# Schematic.net
KiCad netlist of a schematic drawn in EAGLE
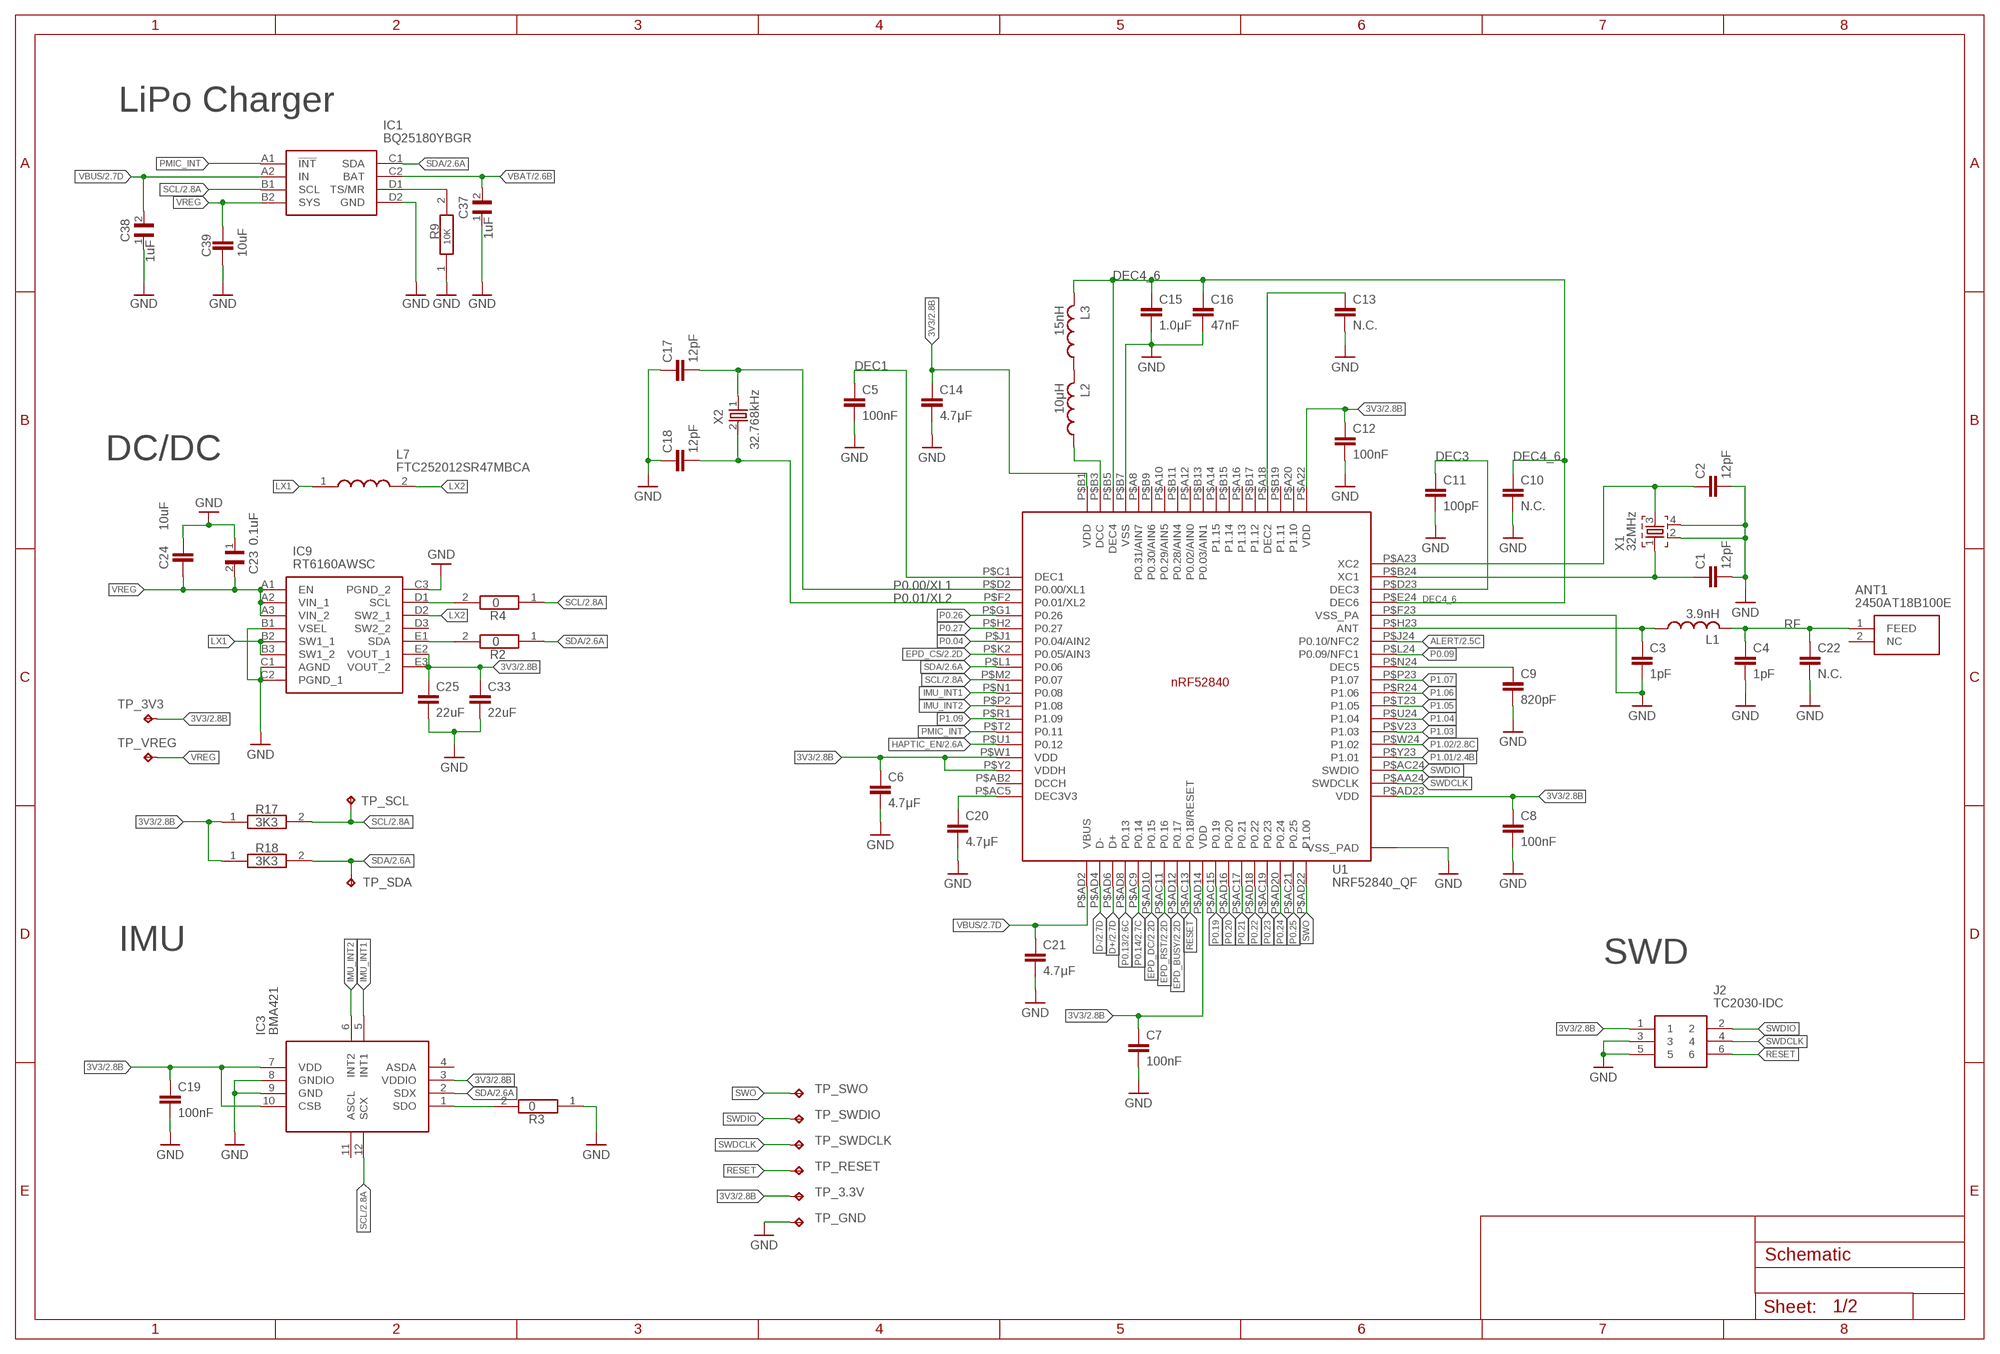
[diagram p0: schematic, sheet 1]
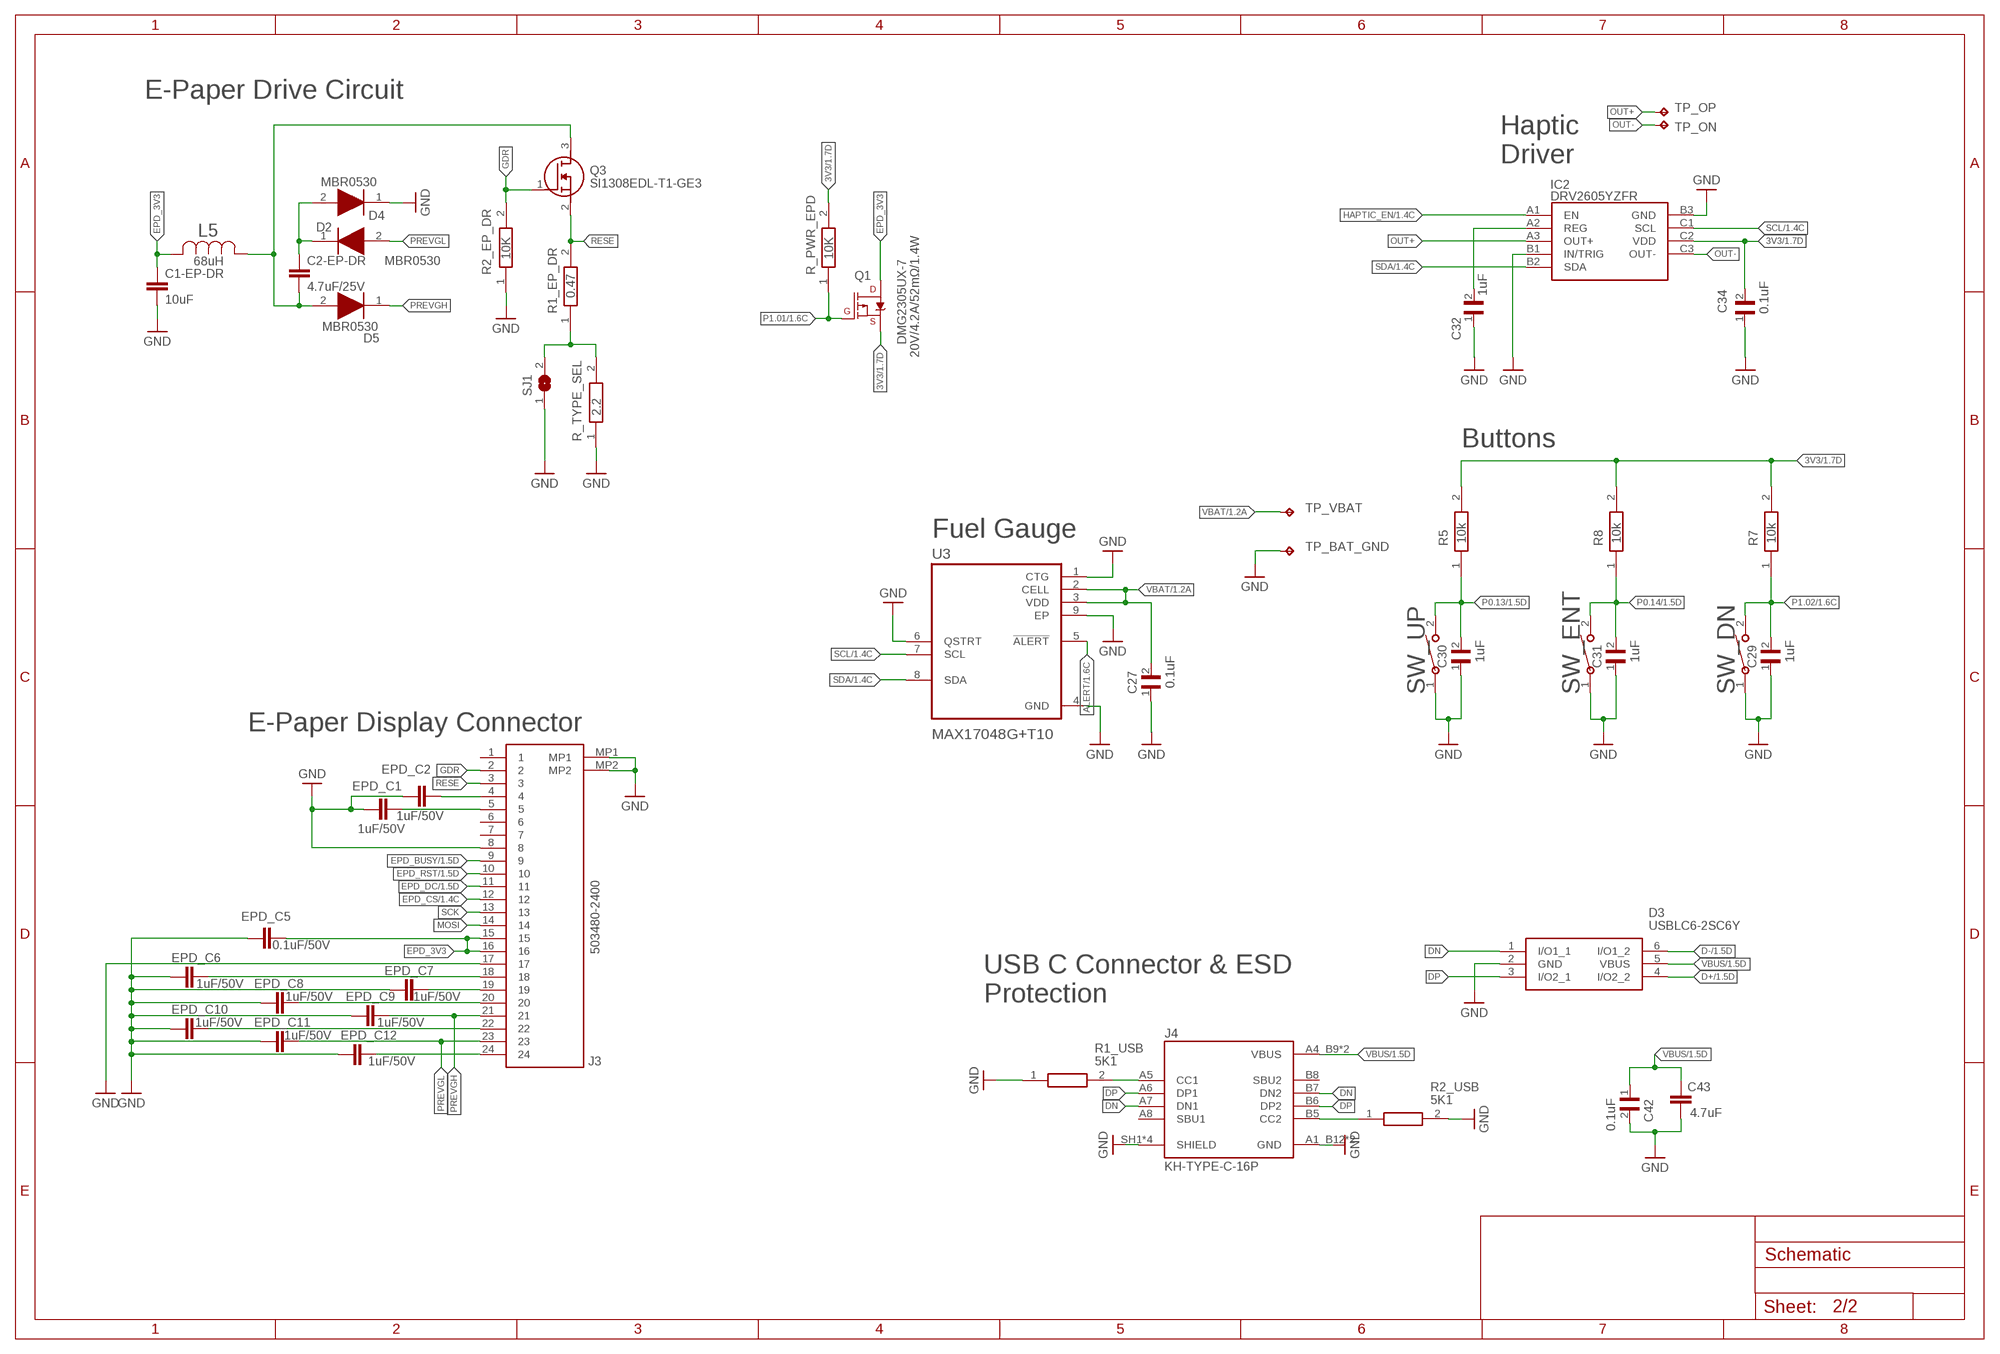
[diagram p1: schematic, sheet 2]

(export (version "E")
  (design (tool "Eeschema 10.0.6"))
  (components
    (comp (ref "C1-EP-DR")
      (value "10uF")
      (footprint "eagle-import:PERFECT_0402_0402")
      (libsource (lib "eagle-import") (part "PERFECT_0402_CAP_0402"))
    )
    (comp (ref "C2-EP-DR")
      (value "4.7uF/25V")
      (footprint "eagle-import:PERFECT_0402_0402")
      (libsource (lib "eagle-import") (part "PERFECT_0402_CAP_0402"))
    )
    (comp (ref "C27")
      (value "0.1uF")
      (footprint "eagle-import:GRM011R60J152KE01L_1_0201")
      (libsource (lib "eagle-import") (part "GRM011R60J152KE01L_1_GRM011R60J152KE01L"))
    )
    (comp (ref "C29")
      (value "1uF")
      (footprint "eagle-import:GRM011R60J152KE01L_1_0201")
      (libsource (lib "eagle-import") (part "GRM011R60J152KE01L_1_GRM011R60J152KE01L"))
    )
    (comp (ref "C30")
      (value "1uF")
      (footprint "eagle-import:GRM011R60J152KE01L_1_0201")
      (libsource (lib "eagle-import") (part "GRM011R60J152KE01L_1_GRM011R60J152KE01L"))
    )
    (comp (ref "C31")
      (value "1uF")
      (footprint "eagle-import:GRM011R60J152KE01L_1_0201")
      (libsource (lib "eagle-import") (part "GRM011R60J152KE01L_1_GRM011R60J152KE01L"))
    )
    (comp (ref "C32")
      (value "1uF")
      (footprint "eagle-import:GRM011R60J152KE01L_1_0201")
      (libsource (lib "eagle-import") (part "GRM011R60J152KE01L_1_GRM011R60J152KE01L"))
    )
    (comp (ref "C34")
      (value "0.1uF")
      (footprint "eagle-import:GRM011R60J152KE01L_1_0201")
      (libsource (lib "eagle-import") (part "GRM011R60J152KE01L_1_GRM011R60J152KE01L"))
    )
    (comp (ref "C42")
      (value "0.1uF")
      (footprint "eagle-import:GRM011R60J152KE01L_1_0201")
      (libsource (lib "eagle-import") (part "GRM011R60J152KE01L_1_GRM011R60J152KE01L"))
    )
    (comp (ref "C43")
      (value "4.7uF")
      (footprint "eagle-import:PERFECT_0402_0402")
      (libsource (lib "eagle-import") (part "PERFECT_0402_CAP_0402"))
    )
    (comp (ref "D2")
      (value "MBR0530")
      (footprint "eagle-import:ESP32_C6_LIBRARY_5_SOD3716X135N")
      (fields (field (name "MF") "ON Semiconductor"))
      (libsource (lib "eagle-import") (part "ESP32_C6_LIBRARY_5_MBR0530"))
    )
    (comp (ref "D3")
      (value "USBLC6-2SC6Y")
      (footprint "eagle-import:ESP32_C6_LIBRARY_3_SOT95P280X145-6N")
      (fields (field (name "MF") "STMicroelectronics"))
      (libsource (lib "eagle-import") (part "ESP32_C6_LIBRARY_3_USBLC6-2SC6Y"))
    )
    (comp (ref "D4")
      (value "MBR0530")
      (footprint "eagle-import:ESP32_C6_LIBRARY_5_SOD3716X135N")
      (fields (field (name "MF") "ON Semiconductor"))
      (libsource (lib "eagle-import") (part "ESP32_C6_LIBRARY_5_MBR0530"))
    )
    (comp (ref "D5")
      (value "MBR0530")
      (footprint "eagle-import:ESP32_C6_LIBRARY_5_SOD3716X135N")
      (fields (field (name "MF") "ON Semiconductor"))
      (libsource (lib "eagle-import") (part "ESP32_C6_LIBRARY_5_MBR0530"))
    )
    (comp (ref "EPD_C1")
      (value "1uF/50V")
      (footprint "eagle-import:PERFECT_0402_0402")
      (libsource (lib "eagle-import") (part "PERFECT_0402_CAP_0402"))
    )
    (comp (ref "EPD_C2")
      (value "1uF/50V")
      (footprint "eagle-import:PERFECT_0402_0402")
      (libsource (lib "eagle-import") (part "PERFECT_0402_CAP_0402"))
    )
    (comp (ref "EPD_C5")
      (value "0.1uF/50V")
      (footprint "eagle-import:PERFECT_0402_0402")
      (libsource (lib "eagle-import") (part "PERFECT_0402_CAP_0402"))
    )
    (comp (ref "EPD_C6")
      (value "1uF/50V")
      (footprint "eagle-import:PERFECT_0402_0402")
      (libsource (lib "eagle-import") (part "PERFECT_0402_CAP_0402"))
    )
    (comp (ref "EPD_C7")
      (value "1uF/50V")
      (footprint "eagle-import:PERFECT_0402_0402")
      (libsource (lib "eagle-import") (part "PERFECT_0402_CAP_0402"))
    )
    (comp (ref "EPD_C8")
      (value "1uF/50V")
      (footprint "eagle-import:PERFECT_0402_0402")
      (libsource (lib "eagle-import") (part "PERFECT_0402_CAP_0402"))
    )
    (comp (ref "EPD_C9")
      (value "1uF/50V")
      (footprint "eagle-import:PERFECT_0402_0402")
      (libsource (lib "eagle-import") (part "PERFECT_0402_CAP_0402"))
    )
    (comp (ref "EPD_C10")
      (value "1uF/50V")
      (footprint "eagle-import:PERFECT_0402_0402")
      (libsource (lib "eagle-import") (part "PERFECT_0402_CAP_0402"))
    )
    (comp (ref "EPD_C11")
      (value "1uF/50V")
      (footprint "eagle-import:PERFECT_0402_0402")
      (libsource (lib "eagle-import") (part "PERFECT_0402_CAP_0402"))
    )
    (comp (ref "EPD_C12")
      (value "1uF/50V")
      (footprint "eagle-import:PERFECT_0402_0402")
      (libsource (lib "eagle-import") (part "PERFECT_0402_CAP_0402"))
    )
    (comp (ref "IC2")
      (value "DRV2605YZFR")
      (footprint "eagle-import:DRV2605YZFR_BGA9C50P3X3_144X144X62")
      (libsource (lib "eagle-import") (part "DRV2605YZFR_DRV2605YZFR"))
    )
    (comp (ref "J3")
      (value "503480-2400")
      (footprint "eagle-import:503480-2400_5034802400")
      (fields (field (name "MOUSER_PART_NUMBER") "538-503480-2400"))
      (libsource (lib "eagle-import") (part "503480-2400_503480-2400"))
    )
    (comp (ref "J4")
      (value "KH-TYPE-C-16P")
      (footprint "eagle-import:KH-TYPE-C-16P_KINGHELM_KH-TYPE-C-16P")
      (fields (field (name "MF") "kinghelm"))
      (libsource (lib "eagle-import") (part "KH-TYPE-C-16P_KH-TYPE-C-16P"))
    )
    (comp (ref "L5")
      (value "68uH")
      (footprint "eagle-import:ESP32_C6_LIBRARY_2_IND_4828-WE-TPC_WRE")
      (fields
        (field (name "MANUFACTURER_PART_NUMBER") "744043680")
        (field (name "COPYRIGHT") "Copyright (C) 2024 Ultra Librarian. All rights reserved.")
      )
      (libsource (lib "eagle-import") (part "ESP32_C6_LIBRARY_2_744043680IND_4828-WE-TPC_WRE"))
    )
    (comp (ref "Q1")
      (value "20V/4.2A/52mΩ/1.4W")
      (footprint "eagle-import:ESP32_C6_LIBRARY_4_ESP32_C6_LIBRARY_4_ESP32_C6_LIBRARY_4_ESP32_C6_LIBRARY_4_ESP32_WROVER_SPARKFUN-DISCRETESEMI_SOT23-3")
      (libsource (lib "eagle-import") (part "ESP32_C6_LIBRARY_4_ESP32_WROVER_SPARKFUN-DISCRETESEMI_MOSFET_PCH-DMG2305UX-7"))
    )
    (comp (ref "Q3")
      (value "SI1308EDL-T1-GE3")
      (footprint "eagle-import:ESP32_C6_LIBRARY_6_SOT65P210X110-3N")
      (fields (field (name "MF") "Vishay Siliconix"))
      (libsource (lib "eagle-import") (part "ESP32_C6_LIBRARY_6_SI1308EDL-T1-GE3"))
    )
    (comp (ref "R1_EP_DR")
      (value "0.47")
      (footprint "eagle-import:CPF0201D7K68C1_0201")
      (libsource (lib "eagle-import") (part "CPF0201D7K68C1_CPF0201D7K68C1"))
    )
    (comp (ref "R1_USB")
      (value "5K1")
      (footprint "eagle-import:CPF0201D7K68C1_0201")
      (libsource (lib "eagle-import") (part "CPF0201D7K68C1_CPF0201D7K68C1"))
    )
    (comp (ref "R2_EP_DR")
      (value "10K")
      (footprint "eagle-import:CPF0201D7K68C1_0201")
      (libsource (lib "eagle-import") (part "CPF0201D7K68C1_CPF0201D7K68C1"))
    )
    (comp (ref "R2_USB")
      (value "5K1")
      (footprint "eagle-import:CPF0201D7K68C1_0201")
      (libsource (lib "eagle-import") (part "CPF0201D7K68C1_CPF0201D7K68C1"))
    )
    (comp (ref "R5")
      (value "10k")
      (footprint "eagle-import:CPF0201D7K68C1_0201")
      (libsource (lib "eagle-import") (part "CPF0201D7K68C1_CPF0201D7K68C1"))
    )
    (comp (ref "R7")
      (value "10k")
      (footprint "eagle-import:CPF0201D7K68C1_0201")
      (libsource (lib "eagle-import") (part "CPF0201D7K68C1_CPF0201D7K68C1"))
    )
    (comp (ref "R8")
      (value "10k")
      (footprint "eagle-import:CPF0201D7K68C1_0201")
      (libsource (lib "eagle-import") (part "CPF0201D7K68C1_CPF0201D7K68C1"))
    )
    (comp (ref "R_PWR_EPD")
      (value "10K")
      (footprint "eagle-import:CPF0201D7K68C1_0201")
      (libsource (lib "eagle-import") (part "CPF0201D7K68C1_CPF0201D7K68C1"))
    )
    (comp (ref "R_TYPE_SEL")
      (value "2.2")
      (footprint "eagle-import:CPF0201D7K68C1_0201")
      (libsource (lib "eagle-import") (part "CPF0201D7K68C1_CPF0201D7K68C1"))
    )
    (comp (ref "SJ1")
      (value "ESP32_C6_LIBRARY_7_JUMPER_SJ")
      (footprint "eagle-import:ESP32_C6_LIBRARY_7_JUMPER_SJ")
      (libsource (lib "eagle-import") (part "ESP32_C6_LIBRARY_7_JUMPER_SJ"))
    )
    (comp (ref "SW_DN")
      (value "2025-10-22_07-23-44_LIBRARY_EVP-AKE31ASW_EVP-AKE31A_PAN")
      (footprint "eagle-import:2025-10-22_07-23-44_LIBRARY_SW_EVP-AKE31A_PAN")
      (fields
        (field (name "MANUFACTURER_PART_NUMBER") "EVP-AKE31A")
        (field (name "COPYRIGHT") "Copyright (C) 2025 Ultra Librarian. All rights reserved.")
      )
      (libsource (lib "eagle-import") (part "2025-10-22_07-23-44_LIBRARY_EVP-AKE31ASW_EVP-AKE31A_PAN"))
    )
    (comp (ref "SW_ENT")
      (value "2025-10-22_07-23-44_LIBRARY_EVP-AKE31ASW_EVP-AKE31A_PAN")
      (footprint "eagle-import:2025-10-22_07-23-44_LIBRARY_SW_EVP-AKE31A_PAN")
      (fields
        (field (name "MANUFACTURER_PART_NUMBER") "EVP-AKE31A")
        (field (name "COPYRIGHT") "Copyright (C) 2025 Ultra Librarian. All rights reserved.")
      )
      (libsource (lib "eagle-import") (part "2025-10-22_07-23-44_LIBRARY_EVP-AKE31ASW_EVP-AKE31A_PAN"))
    )
    (comp (ref "SW_UP")
      (value "2025-10-22_07-23-44_LIBRARY_EVP-AKE31ASW_EVP-AKE31A_PAN")
      (footprint "eagle-import:2025-10-22_07-23-44_LIBRARY_SW_EVP-AKE31A_PAN")
      (fields
        (field (name "MANUFACTURER_PART_NUMBER") "EVP-AKE31A")
        (field (name "COPYRIGHT") "Copyright (C) 2025 Ultra Librarian. All rights reserved.")
      )
      (libsource (lib "eagle-import") (part "2025-10-22_07-23-44_LIBRARY_EVP-AKE31ASW_EVP-AKE31A_PAN"))
    )
    (comp (ref "TP_BAT_GND")
      (value "HECTOR_WATCH_1_TPTP20R")
      (footprint "eagle-import:HECTOR_WATCH_1_TP20R")
      (libsource (lib "eagle-import") (part "HECTOR_WATCH_1_TPTP20R"))
    )
    (comp (ref "TP_ON")
      (value "HECTOR_WATCH_1_TPTP20R")
      (footprint "eagle-import:HECTOR_WATCH_1_TP20R")
      (libsource (lib "eagle-import") (part "HECTOR_WATCH_1_TPTP20R"))
    )
    (comp (ref "TP_OP")
      (value "HECTOR_WATCH_1_TPTP20R")
      (footprint "eagle-import:HECTOR_WATCH_1_TP20R")
      (libsource (lib "eagle-import") (part "HECTOR_WATCH_1_TPTP20R"))
    )
    (comp (ref "TP_VBAT")
      (value "HECTOR_WATCH_1_TPTP20R")
      (footprint "eagle-import:HECTOR_WATCH_1_TP20R")
      (libsource (lib "eagle-import") (part "HECTOR_WATCH_1_TPTP20R"))
    )
    (comp (ref "U3")
      (value "MAX17048G+T10")
      (footprint "eagle-import:ESP32_C6_LIBRARY_SON50P200X200X80-9N")
      (fields (field (name "MF") "Analog Devices"))
      (libsource (lib "eagle-import") (part "ESP32_C6_LIBRARY_MAX17048G+T10"))
    )
    (comp (ref "ANT1")
      (value "2450AT18B100E")
      (footprint "eagle-import:2450AT18B100E_ANTC3216X140N")
      (fields (field (name "MOUSER_PART_NUMBER") "609-2450AT18B100E"))
      (libsource (lib "eagle-import") (part "2450AT18B100E_2450AT18B100E"))
    )
    (comp (ref "C1")
      (value "12pF")
      (footprint "eagle-import:PERFECT_0402_0402")
      (libsource (lib "eagle-import") (part "PERFECT_0402_CAP_0402"))
    )
    (comp (ref "C2")
      (value "12pF")
      (footprint "eagle-import:PERFECT_0402_0402")
      (libsource (lib "eagle-import") (part "PERFECT_0402_CAP_0402"))
    )
    (comp (ref "C3")
      (value "1pF")
      (footprint "eagle-import:PERFECT_0402_0402")
      (libsource (lib "eagle-import") (part "PERFECT_0402_CAP_0402"))
    )
    (comp (ref "C4")
      (value "1pF")
      (footprint "eagle-import:PERFECT_0402_0402")
      (libsource (lib "eagle-import") (part "PERFECT_0402_CAP_0402"))
    )
    (comp (ref "C5")
      (value "100nF")
      (footprint "eagle-import:PERFECT_0402_0402")
      (libsource (lib "eagle-import") (part "PERFECT_0402_CAP_0402"))
    )
    (comp (ref "C6")
      (value "4.7μF")
      (footprint "eagle-import:PERFECT_0402_0402")
      (libsource (lib "eagle-import") (part "PERFECT_0402_CAP_0402"))
    )
    (comp (ref "C7")
      (value "100nF")
      (footprint "eagle-import:PERFECT_0402_0402")
      (libsource (lib "eagle-import") (part "PERFECT_0402_CAP_0402"))
    )
    (comp (ref "C8")
      (value "100nF")
      (footprint "eagle-import:PERFECT_0402_0402")
      (libsource (lib "eagle-import") (part "PERFECT_0402_CAP_0402"))
    )
    (comp (ref "C9")
      (value "820pF")
      (footprint "eagle-import:PERFECT_0402_0402")
      (libsource (lib "eagle-import") (part "PERFECT_0402_CAP_0402"))
    )
    (comp (ref "C10")
      (value "N.C.")
      (footprint "eagle-import:PERFECT_0402_0402")
      (libsource (lib "eagle-import") (part "PERFECT_0402_CAP_0402"))
    )
    (comp (ref "C11")
      (value "100pF")
      (footprint "eagle-import:PERFECT_0402_0402")
      (libsource (lib "eagle-import") (part "PERFECT_0402_CAP_0402"))
    )
    (comp (ref "C12")
      (value "100nF")
      (footprint "eagle-import:PERFECT_0402_0402")
      (libsource (lib "eagle-import") (part "PERFECT_0402_CAP_0402"))
    )
    (comp (ref "C13")
      (value "N.C.")
      (footprint "eagle-import:PERFECT_0402_0402")
      (libsource (lib "eagle-import") (part "PERFECT_0402_CAP_0402"))
    )
    (comp (ref "C14")
      (value "4.7μF")
      (footprint "eagle-import:PERFECT_0402_0402")
      (libsource (lib "eagle-import") (part "PERFECT_0402_CAP_0402"))
    )
    (comp (ref "C15")
      (value "1.0μF")
      (footprint "eagle-import:PERFECT_0402_0402")
      (libsource (lib "eagle-import") (part "PERFECT_0402_CAP_0402"))
    )
    (comp (ref "C16")
      (value "47nF")
      (footprint "eagle-import:PERFECT_0402_0402")
      (libsource (lib "eagle-import") (part "PERFECT_0402_CAP_0402"))
    )
    (comp (ref "C17")
      (value "12pF")
      (footprint "eagle-import:PERFECT_0402_0402")
      (libsource (lib "eagle-import") (part "PERFECT_0402_CAP_0402"))
    )
    (comp (ref "C18")
      (value "12pF")
      (footprint "eagle-import:PERFECT_0402_0402")
      (libsource (lib "eagle-import") (part "PERFECT_0402_CAP_0402"))
    )
    (comp (ref "C19")
      (value "100nF")
      (footprint "eagle-import:PERFECT_0402_0402")
      (libsource (lib "eagle-import") (part "PERFECT_0402_CAP_0402"))
    )
    (comp (ref "C20")
      (value "4.7μF")
      (footprint "eagle-import:PERFECT_0402_0402")
      (libsource (lib "eagle-import") (part "PERFECT_0402_CAP_0402"))
    )
    (comp (ref "C21")
      (value "4.7μF")
      (footprint "eagle-import:PERFECT_0402_0402")
      (libsource (lib "eagle-import") (part "PERFECT_0402_CAP_0402"))
    )
    (comp (ref "C22")
      (value "N.C.")
      (footprint "eagle-import:PERFECT_0402_0402")
      (libsource (lib "eagle-import") (part "PERFECT_0402_CAP_0402"))
    )
    (comp (ref "C23")
      (value "0.1uF")
      (footprint "eagle-import:GRM011R60J152KE01L_1_0201")
      (libsource (lib "eagle-import") (part "GRM011R60J152KE01L_1_GRM011R60J152KE01L"))
    )
    (comp (ref "C24")
      (value "10uF")
      (footprint "eagle-import:PERFECT_0402_0402")
      (libsource (lib "eagle-import") (part "PERFECT_0402_CAP_0402"))
    )
    (comp (ref "C25")
      (value "22uF")
      (footprint "eagle-import:PERFECT_0402_0402")
      (libsource (lib "eagle-import") (part "PERFECT_0402_CAP_0402"))
    )
    (comp (ref "C33")
      (value "22uF")
      (footprint "eagle-import:PERFECT_0402_0402")
      (libsource (lib "eagle-import") (part "PERFECT_0402_CAP_0402"))
    )
    (comp (ref "C37")
      (value "1uF")
      (footprint "eagle-import:GRM011R60J152KE01L_1_0201")
      (libsource (lib "eagle-import") (part "GRM011R60J152KE01L_1_GRM011R60J152KE01L"))
    )
    (comp (ref "C38")
      (value "1uF")
      (footprint "eagle-import:GRM011R60J152KE01L_1_0201")
      (libsource (lib "eagle-import") (part "GRM011R60J152KE01L_1_GRM011R60J152KE01L"))
    )
    (comp (ref "C39")
      (value "10uF")
      (footprint "eagle-import:NORDIC_NRF_3_RESC0402_N")
      (libsource (lib "eagle-import") (part "NORDIC_NRF_3_CAPACITOR_0402_N"))
    )
    (comp (ref "IC1")
      (value "BQ25180YBGR")
      (footprint "eagle-import:BQ25180YBGR_BGA8C40P2X4_100X155X50")
      (fields (field (name "MOUSER_PART_NUMBER") "595-BQ25180YBGR"))
      (libsource (lib "eagle-import") (part "BQ25180YBGR_BQ25180YBGR"))
    )
    (comp (ref "IC3")
      (value "BMA421")
      (footprint "eagle-import:BMA423_BMA423")
      (fields (field (name "ARROW_PART_NUMBER") "BMA423") (field (name "MOUSER_PART_NUMBER") "262-BMA423"))
      (libsource (lib "eagle-import") (part "BMA423_BMA423"))
    )
    (comp (ref "IC9")
      (value "RT6160AWSC")
      (footprint "eagle-import:RT6160AWSC_BGA15C40P3X5_140X230X60")
      (fields (field (name "MOUSER_PART_NUMBER") "835-RT6160AWSC"))
      (libsource (lib "eagle-import") (part "RT6160AWSC_RT6160AWSC"))
    )
    (comp (ref "J2")
      (value "TC2030-IDC")
      (footprint "eagle-import:TC2030-IDC_TC2030IDC")
      (libsource (lib "eagle-import") (part "TC2030-IDC_TC2030-IDC"))
    )
    (comp (ref "L1")
      (value "3.9nH")
      (footprint "eagle-import:NORDIC_NRF_2_RESC0402_L")
      (libsource (lib "eagle-import") (part "NORDIC_NRF_2_INDUCTOR_0402_L"))
    )
    (comp (ref "L2")
      (value "10μH")
      (footprint "eagle-import:NORDIC_NRF_2_RESC0402_L")
      (libsource (lib "eagle-import") (part "NORDIC_NRF_2_INDUCTOR_0402_L"))
    )
    (comp (ref "L3")
      (value "15nH")
      (footprint "eagle-import:NORDIC_NRF_2_RESC0402_L")
      (libsource (lib "eagle-import") (part "NORDIC_NRF_2_INDUCTOR_0402_L"))
    )
    (comp (ref "L7")
      (value "FTC252012SR47MBCA")
      (footprint "eagle-import:MLP2016SR47MT0S1_INDC2016X100N")
      (libsource (lib "eagle-import") (part "MLP2016SR47MT0S1_FTC252012SR47MBCA"))
    )
    (comp (ref "R2")
      (value "0")
      (footprint "eagle-import:CPF0201D7K68C1_0201")
      (libsource (lib "eagle-import") (part "CPF0201D7K68C1_CPF0201D7K68C1"))
    )
    (comp (ref "R3")
      (value "0")
      (footprint "eagle-import:CPF0201D7K68C1_0201")
      (libsource (lib "eagle-import") (part "CPF0201D7K68C1_CPF0201D7K68C1"))
    )
    (comp (ref "R4")
      (value "0")
      (footprint "eagle-import:CPF0201D7K68C1_0201")
      (libsource (lib "eagle-import") (part "CPF0201D7K68C1_CPF0201D7K68C1"))
    )
    (comp (ref "R9")
      (value "10K")
      (footprint "eagle-import:CPF0201D7K68C1_0201")
      (libsource (lib "eagle-import") (part "CPF0201D7K68C1_CPF0201D7K68C1"))
    )
    (comp (ref "R17")
      (value "3K3")
      (footprint "eagle-import:CPF0201D7K68C1_0201")
      (libsource (lib "eagle-import") (part "CPF0201D7K68C1_CPF0201D7K68C1"))
    )
    (comp (ref "R18")
      (value "3K3")
      (footprint "eagle-import:CPF0201D7K68C1_0201")
      (libsource (lib "eagle-import") (part "CPF0201D7K68C1_CPF0201D7K68C1"))
    )
    (comp (ref "TP_3.3V")
      (value "HECTOR_WATCH_1_TPTP20R")
      (footprint "eagle-import:HECTOR_WATCH_1_TP20R")
      (libsource (lib "eagle-import") (part "HECTOR_WATCH_1_TPTP20R"))
    )
    (comp (ref "TP_3V3")
      (value "HECTOR_WATCH_1_TPTP20R")
      (footprint "eagle-import:HECTOR_WATCH_1_TP20R")
      (libsource (lib "eagle-import") (part "HECTOR_WATCH_1_TPTP20R"))
    )
    (comp (ref "TP_GND")
      (value "HECTOR_WATCH_1_TPTP20R")
      (footprint "eagle-import:HECTOR_WATCH_1_TP20R")
      (libsource (lib "eagle-import") (part "HECTOR_WATCH_1_TPTP20R"))
    )
    (comp (ref "TP_RESET")
      (value "HECTOR_WATCH_1_TPTP20R")
      (footprint "eagle-import:HECTOR_WATCH_1_TP20R")
      (libsource (lib "eagle-import") (part "HECTOR_WATCH_1_TPTP20R"))
    )
    (comp (ref "TP_SCL")
      (value "HECTOR_WATCH_1_TPTP20R")
      (footprint "eagle-import:HECTOR_WATCH_1_TP20R")
      (libsource (lib "eagle-import") (part "HECTOR_WATCH_1_TPTP20R"))
    )
    (comp (ref "TP_SDA")
      (value "HECTOR_WATCH_1_TPTP20R")
      (footprint "eagle-import:HECTOR_WATCH_1_TP20R")
      (libsource (lib "eagle-import") (part "HECTOR_WATCH_1_TPTP20R"))
    )
    (comp (ref "TP_SWDCLK")
      (value "HECTOR_WATCH_1_TPTP20R")
      (footprint "eagle-import:HECTOR_WATCH_1_TP20R")
      (libsource (lib "eagle-import") (part "HECTOR_WATCH_1_TPTP20R"))
    )
    (comp (ref "TP_SWDIO")
      (value "HECTOR_WATCH_1_TPTP20R")
      (footprint "eagle-import:HECTOR_WATCH_1_TP20R")
      (libsource (lib "eagle-import") (part "HECTOR_WATCH_1_TPTP20R"))
    )
    (comp (ref "TP_SWO")
      (value "HECTOR_WATCH_1_TPTP20R")
      (footprint "eagle-import:HECTOR_WATCH_1_TP20R")
      (libsource (lib "eagle-import") (part "HECTOR_WATCH_1_TPTP20R"))
    )
    (comp (ref "TP_VREG")
      (value "HECTOR_WATCH_1_TPTP20R")
      (footprint "eagle-import:HECTOR_WATCH_1_TP20R")
      (libsource (lib "eagle-import") (part "HECTOR_WATCH_1_TPTP20R"))
    )
    (comp (ref "U1")
      (value "NRF52840_QF")
      (footprint "eagle-import:NORDIC_NRF_4_AQFN50P700X700X85_HS-74N")
      (libsource (lib "eagle-import") (part "NORDIC_NRF_4_NRF52840_QF"))
    )
    (comp (ref "X1")
      (value "32MHz")
      (footprint "eagle-import:NORDIC_NRF_BT-XTAL_2016_N")
      (libsource (lib "eagle-import") (part "NORDIC_NRF_XTAL_32MHZ"))
    )
    (comp (ref "X2")
      (value "32.768kHz")
      (footprint "eagle-import:NORDIC_NRF_1_XTAL_3215_N")
      (libsource (lib "eagle-import") (part "NORDIC_NRF_1_XTAL_32KHZ"))
    )
  )
  (nets
    (net (code "1") (name "3V3") (class "Default")
      (node (ref "C12") (pin "1") (pinfunction "1_1") (pintype "passive"))
      (node (ref "C14") (pin "1") (pinfunction "1_1") (pintype "passive"))
      (node (ref "C19") (pin "1") (pinfunction "1_1") (pintype "passive"))
      (node (ref "C25") (pin "1") (pinfunction "1_1") (pintype "passive"))
      (node (ref "C33") (pin "1") (pinfunction "1_1") (pintype "passive"))
      (node (ref "C34") (pin "2") (pinfunction "2_2") (pintype "passive"))
      (node (ref "C6") (pin "1") (pinfunction "1_1") (pintype "passive"))
      (node (ref "C7") (pin "1") (pinfunction "1_1") (pintype "passive"))
      (node (ref "C8") (pin "1") (pinfunction "1_1") (pintype "passive"))
      (node (ref "IC2") (pin "C2") (pinfunction "VDD_C2") (pintype "bidirectional"))
      (node (ref "IC3") (pin "10") (pinfunction "CSB_10") (pintype "bidirectional"))
      (node (ref "IC3") (pin "3") (pinfunction "VDDIO_3") (pintype "bidirectional"))
      (node (ref "IC3") (pin "7") (pinfunction "VDD_7") (pintype "bidirectional"))
      (node (ref "IC9") (pin "E2") (pinfunction "VOUT_1_E2") (pintype "bidirectional"))
      (node (ref "IC9") (pin "E3") (pinfunction "VOUT_2_E3") (pintype "bidirectional"))
      (node (ref "J2") (pin "1") (pinfunction "1_1") (pintype "bidirectional"))
      (node (ref "Q1") (pin "2") (pinfunction "S_2") (pintype "bidirectional"))
      (node (ref "R17") (pin "1") (pinfunction "1_1") (pintype "bidirectional"))
      (node (ref "R18") (pin "1") (pinfunction "1_1") (pintype "bidirectional"))
      (node (ref "R5") (pin "2") (pinfunction "2_2") (pintype "bidirectional"))
      (node (ref "R7") (pin "2") (pinfunction "2_2") (pintype "bidirectional"))
      (node (ref "R8") (pin "2") (pinfunction "2_2") (pintype "bidirectional"))
      (node (ref "R_PWR_EPD") (pin "2") (pinfunction "2_2") (pintype "bidirectional"))
      (node (ref "TP_3.3V") (pin "TP") (pinfunction "TP_TP") (pintype "input"))
      (node (ref "TP_3V3") (pin "TP") (pinfunction "TP_TP") (pintype "input"))
      (node (ref "U1") (pin "P$A22") (pinfunction "VDD_P$A22") (pintype "power_in"))
      (node (ref "U1") (pin "P$AD14") (pinfunction "VDD_P$AD14") (pintype "power_in"))
      (node (ref "U1") (pin "P$AD23") (pinfunction "VDD_P$AD23") (pintype "power_in"))
      (node (ref "U1") (pin "P$B1") (pinfunction "VDD_P$B1") (pintype "power_in"))
      (node (ref "U1") (pin "P$W1") (pinfunction "VDD_P$W1") (pintype "power_in"))
      (node (ref "U1") (pin "P$Y2") (pinfunction "VDDH_P$Y2") (pintype "power_in"))
    )
    (net (code "2") (name "ALERT") (class "Default")
      (node (ref "U1") (pin "P$J24") (pinfunction "P0.10/NFC2_P$J24") (pintype "bidirectional"))
      (node (ref "U3") (pin "5") (pinfunction "~{ALERT}_5") (pintype "output"))
    )
    (net (code "3") (name "D+") (class "Default")
      (node (ref "D3") (pin "4") (pinfunction "I/O2_2_4") (pintype "bidirectional"))
      (node (ref "U1") (pin "P$AD6") (pinfunction "D+_P$AD6") (pintype "bidirectional"))
    )
    (net (code "4") (name "D-") (class "Default")
      (node (ref "D3") (pin "6") (pinfunction "I/O1_2_6") (pintype "bidirectional"))
      (node (ref "U1") (pin "P$AD4") (pinfunction "D-_P$AD4") (pintype "bidirectional"))
    )
    (net (code "5") (name "DEC1") (class "Default")
      (node (ref "C5") (pin "1") (pinfunction "1_1") (pintype "passive"))
      (node (ref "U1") (pin "P$C1") (pinfunction "DEC1_P$C1") (pintype "power_in"))
    )
    (net (code "6") (name "DEC3") (class "Default")
      (node (ref "C11") (pin "1") (pinfunction "1_1") (pintype "passive"))
      (node (ref "U1") (pin "P$D23") (pinfunction "DEC3_P$D23") (pintype "bidirectional"))
    )
    (net (code "7") (name "DEC4_6") (class "Default")
      (node (ref "C10") (pin "1") (pinfunction "1_1") (pintype "passive"))
      (node (ref "C15") (pin "1") (pinfunction "1_1") (pintype "passive"))
      (node (ref "C16") (pin "1") (pinfunction "1_1") (pintype "passive"))
      (node (ref "L3") (pin "2") (pinfunction "2_2") (pintype "passive"))
      (node (ref "U1") (pin "P$B5") (pinfunction "DEC4_P$B5") (pintype "power_in"))
      (node (ref "U1") (pin "P$E24") (pinfunction "DEC6_P$E24") (pintype "bidirectional"))
    )
    (net (code "8") (name "DN") (class "Default")
      (node (ref "D3") (pin "1") (pinfunction "I/O1_1_1") (pintype "bidirectional"))
      (node (ref "J4") (pin "A7") (pinfunction "DN1_A7") (pintype "bidirectional"))
      (node (ref "J4") (pin "B7") (pinfunction "DN2_B7") (pintype "bidirectional"))
    )
    (net (code "9") (name "DP") (class "Default")
      (node (ref "D3") (pin "3") (pinfunction "I/O2_1_3") (pintype "bidirectional"))
      (node (ref "J4") (pin "A6") (pinfunction "DP1_A6") (pintype "bidirectional"))
      (node (ref "J4") (pin "B6") (pinfunction "DP2_B6") (pintype "bidirectional"))
    )
    (net (code "10") (name "EPD_3V3") (class "Default")
      (node (ref "C1-EP-DR") (pin "1") (pinfunction "1_1") (pintype "passive"))
      (node (ref "EPD_C5") (pin "2") (pinfunction "2_2") (pintype "passive"))
      (node (ref "J3") (pin "15") (pinfunction "15_15") (pintype "bidirectional"))
      (node (ref "J3") (pin "16") (pinfunction "16_16") (pintype "bidirectional"))
      (node (ref "L5") (pin "2") (pinfunction "2_2") (pintype "passive"))
      (node (ref "Q1") (pin "3") (pinfunction "D_3") (pintype "bidirectional"))
    )
    (net (code "11") (name "EPD_BUSY") (class "Default")
      (node (ref "J3") (pin "9") (pinfunction "9_9") (pintype "bidirectional"))
      (node (ref "U1") (pin "P$AD12") (pinfunction "P0.17_P$AD12") (pintype "bidirectional"))
    )
    (net (code "12") (name "EPD_CS") (class "Default")
      (node (ref "J3") (pin "12") (pinfunction "12_12") (pintype "bidirectional"))
      (node (ref "U1") (pin "P$K2") (pinfunction "P0.05/AIN3_P$K2") (pintype "bidirectional"))
    )
    (net (code "13") (name "EPD_DC") (class "Default")
      (node (ref "J3") (pin "11") (pinfunction "11_11") (pintype "bidirectional"))
      (node (ref "U1") (pin "P$AD10") (pinfunction "P0.15_P$AD10") (pintype "bidirectional"))
    )
    (net (code "14") (name "EPD_RST") (class "Default")
      (node (ref "J3") (pin "10") (pinfunction "10_10") (pintype "bidirectional"))
      (node (ref "U1") (pin "P$AC11") (pinfunction "P0.16_P$AC11") (pintype "bidirectional"))
    )
    (net (code "15") (name "GDR") (class "Default")
      (node (ref "J3") (pin "2") (pinfunction "2_2") (pintype "bidirectional"))
      (node (ref "Q3") (pin "1") (pinfunction "G_1") (pintype "bidirectional"))
      (node (ref "R2_EP_DR") (pin "2") (pinfunction "2_2") (pintype "bidirectional"))
    )
    (net (code "16") (name "GND") (class "Default")
      (node (ref "C1") (pin "2") (pinfunction "2_2") (pintype "passive"))
      (node (ref "C1-EP-DR") (pin "2") (pinfunction "2_2") (pintype "passive"))
      (node (ref "C10") (pin "2") (pinfunction "2_2") (pintype "passive"))
      (node (ref "C11") (pin "2") (pinfunction "2_2") (pintype "passive"))
      (node (ref "C12") (pin "2") (pinfunction "2_2") (pintype "passive"))
      (node (ref "C13") (pin "2") (pinfunction "2_2") (pintype "passive"))
      (node (ref "C14") (pin "2") (pinfunction "2_2") (pintype "passive"))
      (node (ref "C15") (pin "2") (pinfunction "2_2") (pintype "passive"))
      (node (ref "C16") (pin "2") (pinfunction "2_2") (pintype "passive"))
      (node (ref "C17") (pin "1") (pinfunction "1_1") (pintype "passive"))
      (node (ref "C18") (pin "1") (pinfunction "1_1") (pintype "passive"))
      (node (ref "C19") (pin "2") (pinfunction "2_2") (pintype "passive"))
      (node (ref "C2") (pin "2") (pinfunction "2_2") (pintype "passive"))
      (node (ref "C20") (pin "2") (pinfunction "2_2") (pintype "passive"))
      (node (ref "C21") (pin "2") (pinfunction "2_2") (pintype "passive"))
      (node (ref "C22") (pin "2") (pinfunction "2_2") (pintype "passive"))
      (node (ref "C23") (pin "1") (pinfunction "1_1") (pintype "passive"))
      (node (ref "C24") (pin "1") (pinfunction "1_1") (pintype "passive"))
      (node (ref "C25") (pin "2") (pinfunction "2_2") (pintype "passive"))
      (node (ref "C27") (pin "1") (pinfunction "1_1") (pintype "passive"))
      (node (ref "C29") (pin "1") (pinfunction "1_1") (pintype "passive"))
      (node (ref "C3") (pin "2") (pinfunction "2_2") (pintype "passive"))
      (node (ref "C30") (pin "1") (pinfunction "1_1") (pintype "passive"))
      (node (ref "C31") (pin "1") (pinfunction "1_1") (pintype "passive"))
      (node (ref "C32") (pin "1") (pinfunction "1_1") (pintype "passive"))
      (node (ref "C33") (pin "2") (pinfunction "2_2") (pintype "passive"))
      (node (ref "C34") (pin "1") (pinfunction "1_1") (pintype "passive"))
      (node (ref "C37") (pin "1") (pinfunction "1_1") (pintype "passive"))
      (node (ref "C38") (pin "1") (pinfunction "1_1") (pintype "passive"))
      (node (ref "C39") (pin "2") (pinfunction "2_2") (pintype "passive"))
      (node (ref "C4") (pin "2") (pinfunction "2_2") (pintype "passive"))
      (node (ref "C42") (pin "2") (pinfunction "2_2") (pintype "passive"))
      (node (ref "C43") (pin "1") (pinfunction "1_1") (pintype "passive"))
      (node (ref "C5") (pin "2") (pinfunction "2_2") (pintype "passive"))
      (node (ref "C6") (pin "2") (pinfunction "2_2") (pintype "passive"))
      (node (ref "C7") (pin "2") (pinfunction "2_2") (pintype "passive"))
      (node (ref "C8") (pin "2") (pinfunction "2_2") (pintype "passive"))
      (node (ref "C9") (pin "2") (pinfunction "2_2") (pintype "passive"))
      (node (ref "D3") (pin "2") (pinfunction "GND_2") (pintype "bidirectional"))
      (node (ref "D4") (pin "1") (pinfunction "K_1") (pintype "bidirectional"))
      (node (ref "EPD_C1") (pin "1") (pinfunction "1_1") (pintype "passive"))
      (node (ref "EPD_C10") (pin "1") (pinfunction "1_1") (pintype "passive"))
      (node (ref "EPD_C11") (pin "1") (pinfunction "1_1") (pintype "passive"))
      (node (ref "EPD_C12") (pin "1") (pinfunction "1_1") (pintype "passive"))
      (node (ref "EPD_C2") (pin "1") (pinfunction "1_1") (pintype "passive"))
      (node (ref "EPD_C5") (pin "1") (pinfunction "1_1") (pintype "passive"))
      (node (ref "EPD_C6") (pin "1") (pinfunction "1_1") (pintype "passive"))
      (node (ref "EPD_C7") (pin "1") (pinfunction "1_1") (pintype "passive"))
      (node (ref "EPD_C8") (pin "1") (pinfunction "1_1") (pintype "passive"))
      (node (ref "EPD_C9") (pin "1") (pinfunction "1_1") (pintype "passive"))
      (node (ref "IC1") (pin "D2") (pinfunction "GND_D2") (pintype "bidirectional"))
      (node (ref "IC2") (pin "B1") (pinfunction "IN/TRIG_B1") (pintype "bidirectional"))
      (node (ref "IC2") (pin "B3") (pinfunction "GND_B3") (pintype "bidirectional"))
      (node (ref "IC3") (pin "8") (pinfunction "GNDIO_8") (pintype "bidirectional"))
      (node (ref "IC3") (pin "9") (pinfunction "GND_9") (pintype "bidirectional"))
      (node (ref "IC9") (pin "B1") (pinfunction "VSEL_B1") (pintype "bidirectional"))
      (node (ref "IC9") (pin "C1") (pinfunction "AGND_C1") (pintype "bidirectional"))
      (node (ref "IC9") (pin "C2") (pinfunction "PGND_1_C2") (pintype "bidirectional"))
      (node (ref "IC9") (pin "C3") (pinfunction "PGND_2_C3") (pintype "bidirectional"))
      (node (ref "J2") (pin "3") (pinfunction "3_3") (pintype "bidirectional"))
      (node (ref "J2") (pin "5") (pinfunction "5_5") (pintype "bidirectional"))
      (node (ref "J3") (pin "17") (pinfunction "17_17") (pintype "bidirectional"))
      (node (ref "J3") (pin "8") (pinfunction "8_8") (pintype "bidirectional"))
      (node (ref "J3") (pin "MP1") (pinfunction "MP1_MP1") (pintype "bidirectional"))
      (node (ref "J3") (pin "MP2") (pinfunction "MP2_MP2") (pintype "bidirectional"))
      (node (ref "J4") (pin "A12_B1") (pinfunction "GND_A12_B1") (pintype "power_in"))
      (node (ref "J4") (pin "A1_B12") (pinfunction "GND_A1_B12") (pintype "power_in"))
      (node (ref "J4") (pin "SH1") (pinfunction "SHIELD_SH1") (pintype "passive"))
      (node (ref "J4") (pin "SH2") (pinfunction "SHIELD_SH2") (pintype "passive"))
      (node (ref "J4") (pin "SH3") (pinfunction "SHIELD_SH3") (pintype "passive"))
      (node (ref "J4") (pin "SH4") (pinfunction "SHIELD_SH4") (pintype "passive"))
      (node (ref "R1_USB") (pin "1") (pinfunction "1_1") (pintype "bidirectional"))
      (node (ref "R2_EP_DR") (pin "1") (pinfunction "1_1") (pintype "bidirectional"))
      (node (ref "R2_USB") (pin "2") (pinfunction "2_2") (pintype "bidirectional"))
      (node (ref "R3") (pin "1") (pinfunction "1_1") (pintype "bidirectional"))
      (node (ref "R9") (pin "1") (pinfunction "1_1") (pintype "bidirectional"))
      (node (ref "R_TYPE_SEL") (pin "1") (pinfunction "1_1") (pintype "bidirectional"))
      (node (ref "SJ1") (pin "1") (pinfunction "1_1") (pintype "passive"))
      (node (ref "SW_DN") (pin "1") (pinfunction "1_1") (pintype "passive"))
      (node (ref "SW_ENT") (pin "1") (pinfunction "1_1") (pintype "passive"))
      (node (ref "SW_UP") (pin "1") (pinfunction "1_1") (pintype "passive"))
      (node (ref "TP_BAT_GND") (pin "TP") (pinfunction "TP_TP") (pintype "input"))
      (node (ref "TP_GND") (pin "TP") (pinfunction "TP_TP") (pintype "input"))
      (node (ref "U1") (pin "P$74") (pinfunction "VSS_PAD_P$74") (pintype "bidirectional"))
      (node (ref "U1") (pin "P$75") (pinfunction "VSS_PAD_P$75") (pintype "bidirectional"))
      (node (ref "U1") (pin "P$76") (pinfunction "VSS_PAD_P$76") (pintype "bidirectional"))
      (node (ref "U1") (pin "P$77") (pinfunction "VSS_PAD_P$77") (pintype "bidirectional"))
      (node (ref "U1") (pin "P$78") (pinfunction "VSS_PAD_P$78") (pintype "bidirectional"))
      (node (ref "U1") (pin "P$79") (pinfunction "VSS_PAD_P$79") (pintype "bidirectional"))
      (node (ref "U1") (pin "P$80") (pinfunction "VSS_PAD_P$80") (pintype "bidirectional"))
      (node (ref "U1") (pin "P$81") (pinfunction "VSS_PAD_P$81") (pintype "bidirectional"))
      (node (ref "U1") (pin "P$82") (pinfunction "VSS_PAD_P$82") (pintype "bidirectional"))
      (node (ref "U1") (pin "P$83") (pinfunction "VSS_PAD_P$83") (pintype "bidirectional"))
      (node (ref "U1") (pin "P$84") (pinfunction "VSS_PAD_P$84") (pintype "bidirectional"))
      (node (ref "U1") (pin "P$85") (pinfunction "VSS_PAD_P$85") (pintype "bidirectional"))
      (node (ref "U1") (pin "P$86") (pinfunction "VSS_PAD_P$86") (pintype "bidirectional"))
      (node (ref "U1") (pin "P$87") (pinfunction "VSS_PAD_P$87") (pintype "bidirectional"))
      (node (ref "U1") (pin "P$88") (pinfunction "VSS_PAD_P$88") (pintype "bidirectional"))
      (node (ref "U1") (pin "P$89") (pinfunction "VSS_PAD_P$89") (pintype "bidirectional"))
      (node (ref "U1") (pin "P$90") (pinfunction "VSS_PAD_P$90") (pintype "bidirectional"))
      (node (ref "U1") (pin "P$B7") (pinfunction "VSS_P$B7") (pintype "power_in"))
      (node (ref "U1") (pin "P$F23") (pinfunction "VSS_PA_P$F23") (pintype "bidirectional"))
      (node (ref "U3") (pin "1") (pinfunction "CTG_1") (pintype "power_in"))
      (node (ref "U3") (pin "4") (pinfunction "GND_4") (pintype "power_in"))
      (node (ref "U3") (pin "6") (pinfunction "QSTRT_6") (pintype "input"))
      (node (ref "U3") (pin "9") (pinfunction "EP_9") (pintype "power_in"))
      (node (ref "X1") (pin "2") (pinfunction "2_2") (pintype "passive"))
      (node (ref "X1") (pin "4") (pinfunction "4_4") (pintype "passive"))
    )
    (net (code "17") (name "HAPTIC_EN") (class "Default")
      (node (ref "IC2") (pin "A1") (pinfunction "EN_A1") (pintype "bidirectional"))
      (node (ref "U1") (pin "P$U1") (pinfunction "P0.12_P$U1") (pintype "bidirectional"))
    )
    (net (code "18") (name "IMU_INT1") (class "Default")
      (node (ref "IC3") (pin "5") (pinfunction "INT1_5") (pintype "bidirectional"))
      (node (ref "U1") (pin "P$N1") (pinfunction "P0.08_P$N1") (pintype "bidirectional"))
    )
    (net (code "19") (name "IMU_INT2") (class "Default")
      (node (ref "IC3") (pin "6") (pinfunction "INT2_6") (pintype "bidirectional"))
      (node (ref "U1") (pin "P$P2") (pinfunction "P1.08_P$P2") (pintype "bidirectional"))
    )
    (net (code "20") (name "LX1") (class "Default")
      (node (ref "IC9") (pin "B2") (pinfunction "SW1_1_B2") (pintype "bidirectional"))
      (node (ref "IC9") (pin "B3") (pinfunction "SW1_2_B3") (pintype "bidirectional"))
      (node (ref "L7") (pin "1") (pinfunction "1_1") (pintype "bidirectional"))
    )
    (net (code "21") (name "LX2") (class "Default")
      (node (ref "IC9") (pin "D2") (pinfunction "SW2_1_D2") (pintype "bidirectional"))
      (node (ref "L7") (pin "2") (pinfunction "2_2") (pintype "bidirectional"))
    )
    (net (code "22") (name "MOSI") (class "Default")
      (node (ref "J3") (pin "14") (pinfunction "14_14") (pintype "bidirectional"))
    )
    (net (code "23") (name "Net-(D2-K)") (class "Default")
      (node (ref "C2-EP-DR") (pin "1") (pinfunction "1_1") (pintype "passive"))
      (node (ref "D2") (pin "1") (pinfunction "K_1") (pintype "bidirectional"))
      (node (ref "D4") (pin "2") (pinfunction "A_2") (pintype "bidirectional"))
    )
    (net (code "24") (name "Net-(D5-A)") (class "Default")
      (node (ref "C2-EP-DR") (pin "2") (pinfunction "2_2") (pintype "passive"))
      (node (ref "D5") (pin "2") (pinfunction "A_2") (pintype "bidirectional"))
      (node (ref "L5") (pin "1") (pinfunction "1_1") (pintype "passive"))
      (node (ref "Q3") (pin "3") (pinfunction "D_3") (pintype "bidirectional"))
    )
    (net (code "25") (name "Net-(EPD_C1-Pad2)") (class "Default")
      (node (ref "EPD_C1") (pin "2") (pinfunction "2_2") (pintype "passive"))
      (node (ref "J3") (pin "5") (pinfunction "5_5") (pintype "bidirectional"))
    )
    (net (code "26") (name "Net-(EPD_C2-Pad2)") (class "Default")
      (node (ref "EPD_C2") (pin "2") (pinfunction "2_2") (pintype "passive"))
      (node (ref "J3") (pin "4") (pinfunction "4_4") (pintype "bidirectional"))
    )
    (net (code "27") (name "Net-(EPD_C6-Pad2)") (class "Default")
      (node (ref "EPD_C6") (pin "2") (pinfunction "2_2") (pintype "passive"))
      (node (ref "J3") (pin "18") (pinfunction "18_18") (pintype "bidirectional"))
    )
    (net (code "28") (name "Net-(EPD_C7-Pad2)") (class "Default")
      (node (ref "EPD_C7") (pin "2") (pinfunction "2_2") (pintype "passive"))
      (node (ref "J3") (pin "19") (pinfunction "19_19") (pintype "bidirectional"))
    )
    (net (code "29") (name "Net-(EPD_C8-Pad2)") (class "Default")
      (node (ref "EPD_C8") (pin "2") (pinfunction "2_2") (pintype "passive"))
      (node (ref "J3") (pin "20") (pinfunction "20_20") (pintype "bidirectional"))
    )
    (net (code "30") (name "Net-(EPD_C10-Pad2)") (class "Default")
      (node (ref "EPD_C10") (pin "2") (pinfunction "2_2") (pintype "passive"))
      (node (ref "J3") (pin "22") (pinfunction "22_22") (pintype "bidirectional"))
    )
    (net (code "31") (name "Net-(EPD_C12-Pad2)") (class "Default")
      (node (ref "EPD_C12") (pin "2") (pinfunction "2_2") (pintype "passive"))
      (node (ref "J3") (pin "24") (pinfunction "24_24") (pintype "bidirectional"))
    )
    (net (code "32") (name "Net-(IC1-TS{slash}MR)") (class "Default")
      (node (ref "IC1") (pin "D1") (pinfunction "TS/MR_D1") (pintype "bidirectional"))
      (node (ref "R9") (pin "2") (pinfunction "2_2") (pintype "bidirectional"))
    )
    (net (code "33") (name "Net-(IC2-REG)") (class "Default")
      (node (ref "C32") (pin "2") (pinfunction "2_2") (pintype "passive"))
      (node (ref "IC2") (pin "A2") (pinfunction "REG_A2") (pintype "bidirectional"))
    )
    (net (code "34") (name "Net-(IC3-SDO)") (class "Default")
      (node (ref "IC3") (pin "1") (pinfunction "SDO_1") (pintype "bidirectional"))
      (node (ref "R3") (pin "2") (pinfunction "2_2") (pintype "bidirectional"))
    )
    (net (code "35") (name "Net-(IC9-SCL)") (class "Default")
      (node (ref "IC9") (pin "D1") (pinfunction "SCL_D1") (pintype "bidirectional"))
      (node (ref "R4") (pin "2") (pinfunction "2_2") (pintype "bidirectional"))
    )
    (net (code "36") (name "Net-(IC9-SDA)") (class "Default")
      (node (ref "IC9") (pin "E1") (pinfunction "SDA_E1") (pintype "bidirectional"))
      (node (ref "R2") (pin "2") (pinfunction "2_2") (pintype "bidirectional"))
    )
    (net (code "37") (name "Net-(J4-CC1)") (class "Default")
      (node (ref "J4") (pin "A5") (pinfunction "CC1_A5") (pintype "bidirectional"))
      (node (ref "R1_USB") (pin "2") (pinfunction "2_2") (pintype "bidirectional"))
    )
    (net (code "38") (name "Net-(J4-CC2)") (class "Default")
      (node (ref "J4") (pin "B5") (pinfunction "CC2_B5") (pintype "bidirectional"))
      (node (ref "R2_USB") (pin "1") (pinfunction "1_1") (pintype "bidirectional"))
    )
    (net (code "39") (name "Net-(L2-Pad2)") (class "Default")
      (node (ref "L2") (pin "2") (pinfunction "2_2") (pintype "passive"))
      (node (ref "L3") (pin "1") (pinfunction "1_1") (pintype "passive"))
    )
    (net (code "40") (name "Net-(R1_EP_DR-Pad1)") (class "Default")
      (node (ref "R1_EP_DR") (pin "1") (pinfunction "1_1") (pintype "bidirectional"))
      (node (ref "R_TYPE_SEL") (pin "2") (pinfunction "2_2") (pintype "bidirectional"))
      (node (ref "SJ1") (pin "2") (pinfunction "2_2") (pintype "passive"))
    )
    (net (code "41") (name "Net-(U1-ANT)") (class "Default")
      (node (ref "C3") (pin "1") (pinfunction "1_1") (pintype "passive"))
      (node (ref "L1") (pin "1") (pinfunction "1_1") (pintype "passive"))
      (node (ref "U1") (pin "P$H23") (pinfunction "ANT_P$H23") (pintype "bidirectional"))
    )
    (net (code "42") (name "Net-(U1-DCC)") (class "Default")
      (node (ref "L2") (pin "1") (pinfunction "1_1") (pintype "passive"))
      (node (ref "U1") (pin "P$B3") (pinfunction "DCC_P$B3") (pintype "output"))
    )
    (net (code "43") (name "Net-(U1-DEC2)") (class "Default")
      (node (ref "C13") (pin "1") (pinfunction "1_1") (pintype "passive"))
      (node (ref "U1") (pin "P$A18") (pinfunction "DEC2_P$A18") (pintype "bidirectional"))
    )
    (net (code "44") (name "Net-(U1-DEC3V3)") (class "Default")
      (node (ref "C20") (pin "1") (pinfunction "1_1") (pintype "passive"))
      (node (ref "U1") (pin "P$AC5") (pinfunction "DEC3V3_P$AC5") (pintype "bidirectional"))
    )
    (net (code "45") (name "Net-(U1-DEC5)") (class "Default")
      (node (ref "C9") (pin "1") (pinfunction "1_1") (pintype "passive"))
      (node (ref "U1") (pin "P$N24") (pinfunction "DEC5_P$N24") (pintype "bidirectional"))
    )
    (net (code "46") (name "Net-(U1-XC1)") (class "Default")
      (node (ref "C1") (pin "1") (pinfunction "1_1") (pintype "passive"))
      (node (ref "U1") (pin "P$B24") (pinfunction "XC1_P$B24") (pintype "input"))
      (node (ref "X1") (pin "1") (pinfunction "1_1") (pintype "passive"))
    )
    (net (code "47") (name "Net-(U1-XC2)") (class "Default")
      (node (ref "C2") (pin "1") (pinfunction "1_1") (pintype "passive"))
      (node (ref "U1") (pin "P$A23") (pinfunction "XC2_P$A23") (pintype "output"))
      (node (ref "X1") (pin "3") (pinfunction "3_3") (pintype "passive"))
    )
    (net (code "48") (name "OUT+") (class "Default")
      (node (ref "IC2") (pin "A3") (pinfunction "OUT+_A3") (pintype "bidirectional"))
      (node (ref "TP_OP") (pin "TP") (pinfunction "TP_TP") (pintype "input"))
    )
    (net (code "49") (name "OUT-") (class "Default")
      (node (ref "IC2") (pin "C3") (pinfunction "OUT-_C3") (pintype "bidirectional"))
      (node (ref "TP_ON") (pin "TP") (pinfunction "TP_TP") (pintype "input"))
    )
    (net (code "50") (name "P0.00{slash}XL1") (class "Default")
      (node (ref "C17") (pin "2") (pinfunction "2_2") (pintype "passive"))
      (node (ref "U1") (pin "P$D2") (pinfunction "P0.00/XL1_P$D2") (pintype "bidirectional"))
      (node (ref "X2") (pin "1") (pinfunction "1_1") (pintype "passive"))
    )
    (net (code "51") (name "P0.01{slash}XL2") (class "Default")
      (node (ref "C18") (pin "2") (pinfunction "2_2") (pintype "passive"))
      (node (ref "U1") (pin "P$F2") (pinfunction "P0.01/XL2_P$F2") (pintype "bidirectional"))
      (node (ref "X2") (pin "2") (pinfunction "2_2") (pintype "passive"))
    )
    (net (code "52") (name "P0.04") (class "Default")
      (node (ref "U1") (pin "P$J1") (pinfunction "P0.04/AIN2_P$J1") (pintype "bidirectional"))
    )
    (net (code "53") (name "P0.09") (class "Default")
      (node (ref "U1") (pin "P$L24") (pinfunction "P0.09/NFC1_P$L24") (pintype "bidirectional"))
    )
    (net (code "54") (name "P0.13") (class "Default")
      (node (ref "C30") (pin "2") (pinfunction "2_2") (pintype "passive"))
      (node (ref "R5") (pin "1") (pinfunction "1_1") (pintype "bidirectional"))
      (node (ref "SW_UP") (pin "2") (pinfunction "2_2") (pintype "passive"))
      (node (ref "U1") (pin "P$AD8") (pinfunction "P0.13_P$AD8") (pintype "bidirectional"))
    )
    (net (code "55") (name "P0.14") (class "Default")
      (node (ref "C31") (pin "2") (pinfunction "2_2") (pintype "passive"))
      (node (ref "R8") (pin "1") (pinfunction "1_1") (pintype "bidirectional"))
      (node (ref "SW_ENT") (pin "2") (pinfunction "2_2") (pintype "passive"))
      (node (ref "U1") (pin "P$AC9") (pinfunction "P0.14_P$AC9") (pintype "bidirectional"))
    )
    (net (code "56") (name "P0.19") (class "Default")
      (node (ref "U1") (pin "P$AC15") (pinfunction "P0.19_P$AC15") (pintype "bidirectional"))
    )
    (net (code "57") (name "P0.20") (class "Default")
      (node (ref "U1") (pin "P$AD16") (pinfunction "P0.20_P$AD16") (pintype "bidirectional"))
    )
    (net (code "58") (name "P0.21") (class "Default")
      (node (ref "U1") (pin "P$AC17") (pinfunction "P0.21_P$AC17") (pintype "bidirectional"))
    )
    (net (code "59") (name "P0.22") (class "Default")
      (node (ref "U1") (pin "P$AD18") (pinfunction "P0.22_P$AD18") (pintype "bidirectional"))
    )
    (net (code "60") (name "P0.23") (class "Default")
      (node (ref "U1") (pin "P$AC19") (pinfunction "P0.23_P$AC19") (pintype "bidirectional"))
    )
    (net (code "61") (name "P0.24") (class "Default")
      (node (ref "U1") (pin "P$AD20") (pinfunction "P0.24_P$AD20") (pintype "bidirectional"))
    )
    (net (code "62") (name "P0.25") (class "Default")
      (node (ref "U1") (pin "P$AC21") (pinfunction "P0.25_P$AC21") (pintype "bidirectional"))
    )
    (net (code "63") (name "P0.26") (class "Default")
      (node (ref "U1") (pin "P$G1") (pinfunction "P0.26_P$G1") (pintype "bidirectional"))
    )
    (net (code "64") (name "P0.27") (class "Default")
      (node (ref "U1") (pin "P$H2") (pinfunction "P0.27_P$H2") (pintype "bidirectional"))
    )
    (net (code "65") (name "P1.01") (class "Default")
      (node (ref "Q1") (pin "1") (pinfunction "G_1") (pintype "bidirectional"))
      (node (ref "R_PWR_EPD") (pin "1") (pinfunction "1_1") (pintype "bidirectional"))
      (node (ref "U1") (pin "P$Y23") (pinfunction "P1.01_P$Y23") (pintype "bidirectional"))
    )
    (net (code "66") (name "P1.02") (class "Default")
      (node (ref "C29") (pin "2") (pinfunction "2_2") (pintype "passive"))
      (node (ref "R7") (pin "1") (pinfunction "1_1") (pintype "bidirectional"))
      (node (ref "SW_DN") (pin "2") (pinfunction "2_2") (pintype "passive"))
      (node (ref "U1") (pin "P$W24") (pinfunction "P1.02_P$W24") (pintype "bidirectional"))
    )
    (net (code "67") (name "P1.03") (class "Default")
      (node (ref "U1") (pin "P$V23") (pinfunction "P1.03_P$V23") (pintype "bidirectional"))
    )
    (net (code "68") (name "P1.04") (class "Default")
      (node (ref "U1") (pin "P$U24") (pinfunction "P1.04_P$U24") (pintype "bidirectional"))
    )
    (net (code "69") (name "P1.05") (class "Default")
      (node (ref "U1") (pin "P$T23") (pinfunction "P1.05_P$T23") (pintype "bidirectional"))
    )
    (net (code "70") (name "P1.06") (class "Default")
      (node (ref "U1") (pin "P$R24") (pinfunction "P1.06_P$R24") (pintype "bidirectional"))
    )
    (net (code "71") (name "P1.07") (class "Default")
      (node (ref "U1") (pin "P$P23") (pinfunction "P1.07_P$P23") (pintype "bidirectional"))
    )
    (net (code "72") (name "P1.09") (class "Default")
      (node (ref "U1") (pin "P$R1") (pinfunction "P1.09_P$R1") (pintype "bidirectional"))
    )
    (net (code "73") (name "PMIC_INT") (class "Default")
      (node (ref "IC1") (pin "A1") (pinfunction "~{INT}_A1") (pintype "bidirectional"))
      (node (ref "U1") (pin "P$T2") (pinfunction "P0.11_P$T2") (pintype "bidirectional"))
    )
    (net (code "74") (name "PREVGH") (class "Default")
      (node (ref "D5") (pin "1") (pinfunction "K_1") (pintype "bidirectional"))
      (node (ref "EPD_C9") (pin "2") (pinfunction "2_2") (pintype "passive"))
      (node (ref "J3") (pin "21") (pinfunction "21_21") (pintype "bidirectional"))
    )
    (net (code "75") (name "PREVGL") (class "Default")
      (node (ref "D2") (pin "2") (pinfunction "A_2") (pintype "bidirectional"))
      (node (ref "EPD_C11") (pin "2") (pinfunction "2_2") (pintype "passive"))
      (node (ref "J3") (pin "23") (pinfunction "23_23") (pintype "bidirectional"))
    )
    (net (code "76") (name "RESE") (class "Default")
      (node (ref "J3") (pin "3") (pinfunction "3_3") (pintype "bidirectional"))
      (node (ref "Q3") (pin "2") (pinfunction "S_2") (pintype "bidirectional"))
      (node (ref "R1_EP_DR") (pin "2") (pinfunction "2_2") (pintype "bidirectional"))
    )
    (net (code "77") (name "RESET") (class "Default")
      (node (ref "J2") (pin "6") (pinfunction "6_6") (pintype "bidirectional"))
      (node (ref "TP_RESET") (pin "TP") (pinfunction "TP_TP") (pintype "input"))
      (node (ref "U1") (pin "P$AC13") (pinfunction "P0.18/RESET_P$AC13") (pintype "bidirectional"))
    )
    (net (code "78") (name "RF") (class "Default")
      (node (ref "ANT1") (pin "1") (pinfunction "FEED_1") (pintype "input"))
      (node (ref "C22") (pin "1") (pinfunction "1_1") (pintype "passive"))
      (node (ref "C4") (pin "1") (pinfunction "1_1") (pintype "passive"))
      (node (ref "L1") (pin "2") (pinfunction "2_2") (pintype "passive"))
    )
    (net (code "79") (name "SCK") (class "Default")
      (node (ref "J3") (pin "13") (pinfunction "13_13") (pintype "bidirectional"))
    )
    (net (code "80") (name "SCL") (class "Default")
      (node (ref "IC1") (pin "B1") (pinfunction "SCL_B1") (pintype "bidirectional"))
      (node (ref "IC2") (pin "C1") (pinfunction "SCL_C1") (pintype "bidirectional"))
      (node (ref "IC3") (pin "12") (pinfunction "SCX_12") (pintype "bidirectional"))
      (node (ref "R17") (pin "2") (pinfunction "2_2") (pintype "bidirectional"))
      (node (ref "R4") (pin "1") (pinfunction "1_1") (pintype "bidirectional"))
      (node (ref "TP_SCL") (pin "TP") (pinfunction "TP_TP") (pintype "input"))
      (node (ref "U1") (pin "P$M2") (pinfunction "P0.07_P$M2") (pintype "bidirectional"))
      (node (ref "U3") (pin "7") (pinfunction "SCL_7") (pintype "input"))
    )
    (net (code "81") (name "SDA") (class "Default")
      (node (ref "IC1") (pin "C1") (pinfunction "SDA_C1") (pintype "bidirectional"))
      (node (ref "IC2") (pin "B2") (pinfunction "SDA_B2") (pintype "bidirectional"))
      (node (ref "IC3") (pin "2") (pinfunction "SDX_2") (pintype "bidirectional"))
      (node (ref "R18") (pin "2") (pinfunction "2_2") (pintype "bidirectional"))
      (node (ref "R2") (pin "1") (pinfunction "1_1") (pintype "bidirectional"))
      (node (ref "TP_SDA") (pin "TP") (pinfunction "TP_TP") (pintype "input"))
      (node (ref "U1") (pin "P$L1") (pinfunction "P0.06_P$L1") (pintype "bidirectional"))
      (node (ref "U3") (pin "8") (pinfunction "SDA_8") (pintype "bidirectional"))
    )
    (net (code "82") (name "SWDCLK") (class "Default")
      (node (ref "J2") (pin "4") (pinfunction "4_4") (pintype "bidirectional"))
      (node (ref "TP_SWDCLK") (pin "TP") (pinfunction "TP_TP") (pintype "input"))
      (node (ref "U1") (pin "P$AA24") (pinfunction "SWDCLK_P$AA24") (pintype "input"))
    )
    (net (code "83") (name "SWDIO") (class "Default")
      (node (ref "J2") (pin "2") (pinfunction "2_2") (pintype "bidirectional"))
      (node (ref "TP_SWDIO") (pin "TP") (pinfunction "TP_TP") (pintype "input"))
      (node (ref "U1") (pin "P$AC24") (pinfunction "SWDIO_P$AC24") (pintype "bidirectional"))
    )
    (net (code "84") (name "SWO") (class "Default")
      (node (ref "TP_SWO") (pin "TP") (pinfunction "TP_TP") (pintype "input"))
      (node (ref "U1") (pin "P$AD22") (pinfunction "P1.00_P$AD22") (pintype "bidirectional"))
    )
    (net (code "85") (name "VBAT") (class "Default")
      (node (ref "C27") (pin "2") (pinfunction "2_2") (pintype "passive"))
      (node (ref "C37") (pin "2") (pinfunction "2_2") (pintype "passive"))
      (node (ref "IC1") (pin "C2") (pinfunction "BAT_C2") (pintype "bidirectional"))
      (node (ref "TP_VBAT") (pin "TP") (pinfunction "TP_TP") (pintype "input"))
      (node (ref "U3") (pin "2") (pinfunction "CELL_2") (pintype "power_in"))
      (node (ref "U3") (pin "3") (pinfunction "VDD_3") (pintype "power_in"))
    )
    (net (code "86") (name "VBUS") (class "Default")
      (node (ref "C21") (pin "1") (pinfunction "1_1") (pintype "passive"))
      (node (ref "C38") (pin "2") (pinfunction "2_2") (pintype "passive"))
      (node (ref "C42") (pin "1") (pinfunction "1_1") (pintype "passive"))
      (node (ref "C43") (pin "2") (pinfunction "2_2") (pintype "passive"))
      (node (ref "D3") (pin "5") (pinfunction "VBUS_5") (pintype "bidirectional"))
      (node (ref "IC1") (pin "A2") (pinfunction "IN_A2") (pintype "bidirectional"))
      (node (ref "J4") (pin "A4_B9") (pinfunction "VBUS_A4_B9") (pintype "power_in"))
      (node (ref "J4") (pin "A9_B4") (pinfunction "VBUS_A9_B4") (pintype "power_in"))
      (node (ref "U1") (pin "P$AD2") (pinfunction "VBUS_P$AD2") (pintype "power_in"))
    )
    (net (code "87") (name "VREG") (class "Default")
      (node (ref "C23") (pin "2") (pinfunction "2_2") (pintype "passive"))
      (node (ref "C24") (pin "2") (pinfunction "2_2") (pintype "passive"))
      (node (ref "C39") (pin "1") (pinfunction "1_1") (pintype "passive"))
      (node (ref "IC1") (pin "B2") (pinfunction "SYS_B2") (pintype "bidirectional"))
      (node (ref "IC9") (pin "A1") (pinfunction "EN_A1") (pintype "bidirectional"))
      (node (ref "IC9") (pin "A2") (pinfunction "VIN_1_A2") (pintype "bidirectional"))
      (node (ref "IC9") (pin "A3") (pinfunction "VIN_2_A3") (pintype "bidirectional"))
      (node (ref "TP_VREG") (pin "TP") (pinfunction "TP_TP") (pintype "input"))
    )
    (net (code "88") (name "unconnected-(ANT1-NC-Pad2)") (class "Default")
      (node (ref "ANT1") (pin "2") (pinfunction "NC_2") (pintype "no_connect"))
    )
    (net (code "89") (name "unconnected-(IC3-ASCL-Pad11)") (class "Default")
      (node (ref "IC3") (pin "11") (pinfunction "ASCL_11") (pintype "bidirectional"))
    )
    (net (code "90") (name "unconnected-(IC3-ASDA-Pad4)") (class "Default")
      (node (ref "IC3") (pin "4") (pinfunction "ASDA_4") (pintype "bidirectional"))
    )
    (net (code "91") (name "unconnected-(IC9-SW2_2-PadD3)") (class "Default")
      (node (ref "IC9") (pin "D3") (pinfunction "SW2_2_D3") (pintype "bidirectional"))
    )
    (net (code "92") (name "unconnected-(J3-Pad1)") (class "Default")
      (node (ref "J3") (pin "1") (pinfunction "1_1") (pintype "bidirectional"))
    )
    (net (code "93") (name "unconnected-(J3-Pad6)") (class "Default")
      (node (ref "J3") (pin "6") (pinfunction "6_6") (pintype "bidirectional"))
    )
    (net (code "94") (name "unconnected-(J3-Pad7)") (class "Default")
      (node (ref "J3") (pin "7") (pinfunction "7_7") (pintype "bidirectional"))
    )
    (net (code "95") (name "unconnected-(J4-SBU1-PadA8)") (class "Default")
      (node (ref "J4") (pin "A8") (pinfunction "SBU1_A8") (pintype "bidirectional"))
    )
    (net (code "96") (name "unconnected-(J4-SBU2-PadB8)") (class "Default")
      (node (ref "J4") (pin "B8") (pinfunction "SBU2_B8") (pintype "bidirectional"))
    )
    (net (code "97") (name "unconnected-(U1-DCCH-PadP$AB2)") (class "Default")
      (node (ref "U1") (pin "P$AB2") (pinfunction "DCCH_P$AB2") (pintype "bidirectional"))
    )
    (net (code "98") (name "unconnected-(U1-P0.02{slash}AIN0-PadP$A12)") (class "Default")
      (node (ref "U1") (pin "P$A12") (pinfunction "P0.02/AIN0_P$A12") (pintype "bidirectional"))
    )
    (net (code "99") (name "unconnected-(U1-P0.03{slash}AIN1-PadP$B13)") (class "Default")
      (node (ref "U1") (pin "P$B13") (pinfunction "P0.03/AIN1_P$B13") (pintype "bidirectional"))
    )
    (net (code "100") (name "unconnected-(U1-P0.28{slash}AIN4-PadP$B11)") (class "Default")
      (node (ref "U1") (pin "P$B11") (pinfunction "P0.28/AIN4_P$B11") (pintype "bidirectional"))
    )
    (net (code "101") (name "unconnected-(U1-P0.29{slash}AIN5-PadP$A10)") (class "Default")
      (node (ref "U1") (pin "P$A10") (pinfunction "P0.29/AIN5_P$A10") (pintype "bidirectional"))
    )
    (net (code "102") (name "unconnected-(U1-P0.30{slash}AIN6-PadP$B9)") (class "Default")
      (node (ref "U1") (pin "P$B9") (pinfunction "P0.30/AIN6_P$B9") (pintype "bidirectional"))
    )
    (net (code "103") (name "unconnected-(U1-P0.31{slash}AIN7-PadP$A8)") (class "Default")
      (node (ref "U1") (pin "P$A8") (pinfunction "P0.31/AIN7_P$A8") (pintype "bidirectional"))
    )
    (net (code "104") (name "unconnected-(U1-P1.10-PadP$A20)") (class "Default")
      (node (ref "U1") (pin "P$A20") (pinfunction "P1.10_P$A20") (pintype "bidirectional"))
    )
    (net (code "105") (name "unconnected-(U1-P1.11-PadP$B19)") (class "Default")
      (node (ref "U1") (pin "P$B19") (pinfunction "P1.11_P$B19") (pintype "bidirectional"))
    )
    (net (code "106") (name "unconnected-(U1-P1.12-PadP$B17)") (class "Default")
      (node (ref "U1") (pin "P$B17") (pinfunction "P1.12_P$B17") (pintype "bidirectional"))
    )
    (net (code "107") (name "unconnected-(U1-P1.13-PadP$A16)") (class "Default")
      (node (ref "U1") (pin "P$A16") (pinfunction "P1.13_P$A16") (pintype "bidirectional"))
    )
    (net (code "108") (name "unconnected-(U1-P1.14-PadP$B15)") (class "Default")
      (node (ref "U1") (pin "P$B15") (pinfunction "P1.14_P$B15") (pintype "bidirectional"))
    )
    (net (code "109") (name "unconnected-(U1-P1.15-PadP$A14)") (class "Default")
      (node (ref "U1") (pin "P$A14") (pinfunction "P1.15_P$A14") (pintype "bidirectional"))
    )
  )
)
